# Sheet1.net
KiCad netlist of a schematic drawn in Altium Designer
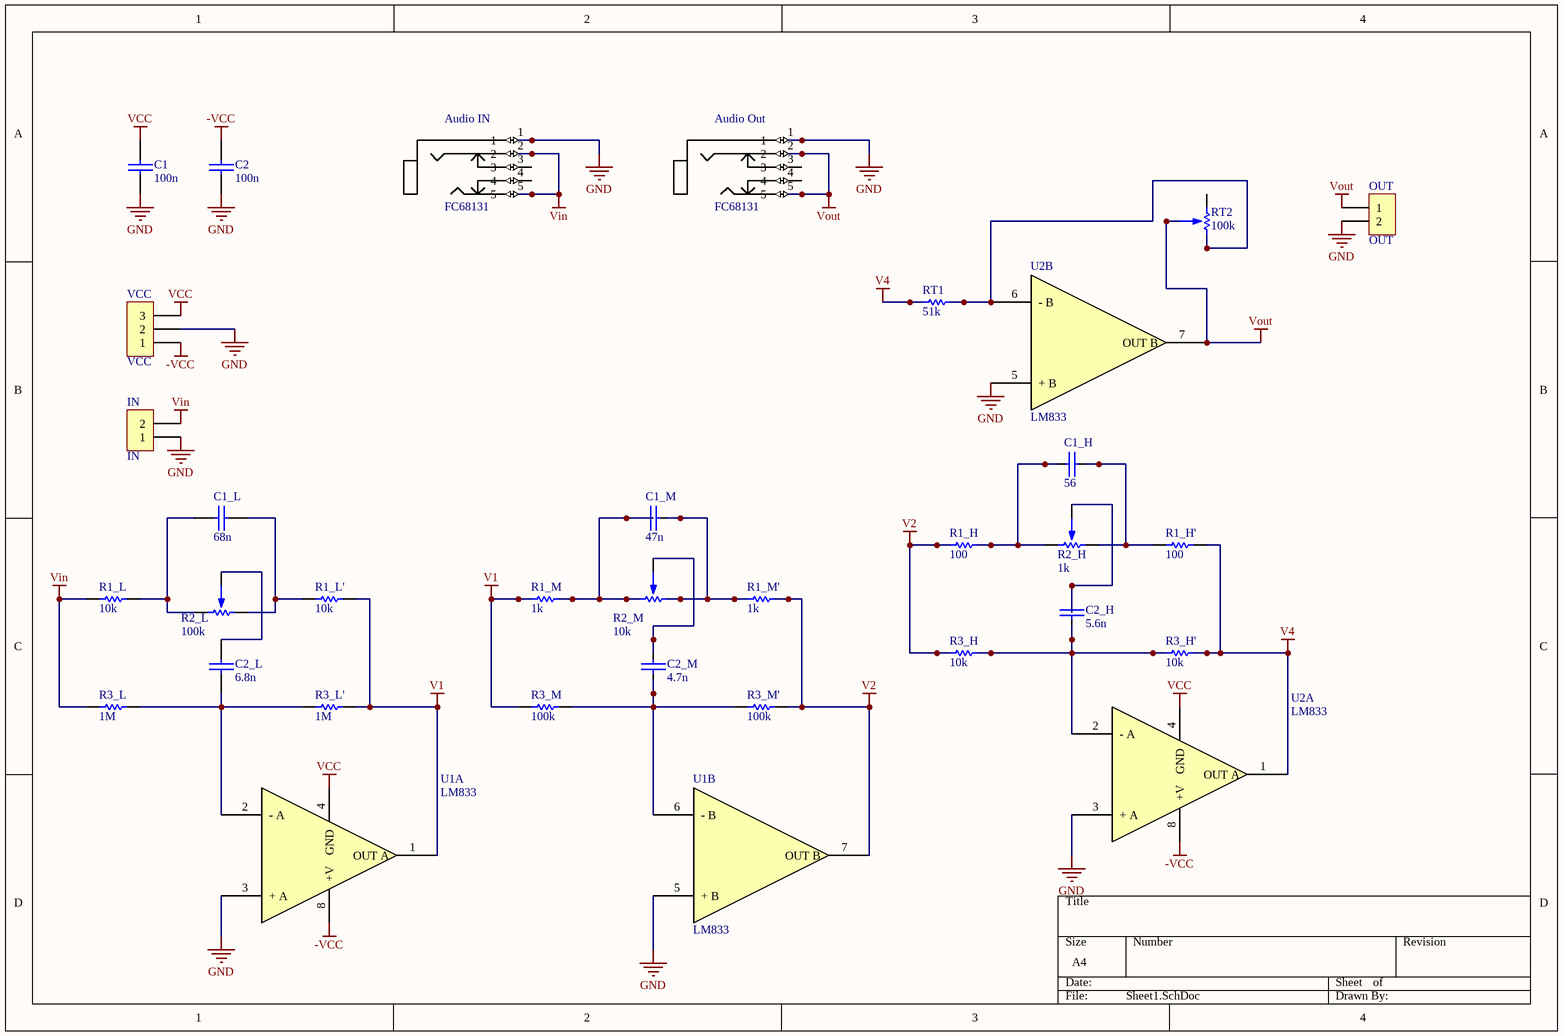
[diagram p0: Sheet1.SchDoc]

(export (version "E")
  (design (tool "Eeschema 10.0.6"))
  (components
    (comp (ref "Audio IN")
      (value "FC68131")
      (footprint "*FC68131-5P")
      (description "Stereo Jack, 3.5mm, 3pos, Pcb")
      (fields (field (name "MF") "Cliff"))
      (libsource (lib "FC68131") (part "FC68131"))
    )
    (comp (ref "Audio Out")
      (value "FC68131")
      (footprint "*FC68131-5P")
      (description "Stereo Jack, 3.5mm, 3pos, Pcb")
      (fields (field (name "MF") "Cliff"))
      (libsource (lib "FC68131") (part "FC68131"))
    )
    (comp (ref "C1") (value "100n") (footprint "0805") (libsource (lib "LIBEBAL") (part "CAP")))
    (comp (ref "C1_H") (value "56") (footprint "0805") (libsource (lib "LIBEBAL") (part "CAP")))
    (comp (ref "C1_L") (value "68n") (footprint "0805") (libsource (lib "LIBEBAL") (part "CAP")))
    (comp (ref "C1_M") (value "47n") (footprint "0805") (libsource (lib "LIBEBAL") (part "CAP")))
    (comp (ref "C2") (value "100n") (footprint "0805") (libsource (lib "LIBEBAL") (part "CAP")))
    (comp (ref "C2_H") (value "5.6n") (footprint "0805") (libsource (lib "LIBEBAL") (part "CAP")))
    (comp (ref "C2_L") (value "6.8n") (footprint "0805") (libsource (lib "LIBEBAL") (part "CAP")))
    (comp (ref "C2_M") (value "4.7n") (footprint "0805") (libsource (lib "LIBEBAL") (part "CAP")))
    (comp (ref "IN") (value "IN") (footprint "BORNERA2") (libsource (lib "LIB PIO IX") (part "BORNERA 2")))
    (comp (ref "OUT") (value "OUT") (footprint "BORNERA2") (libsource (lib "LIBEBAL") (part "BORNERA 2")))
    (comp (ref "R1_H") (value "100") (footprint "0805") (libsource (lib "LIBEBAL") (part "RES")))
    (comp (ref "R1_H'") (value "100") (footprint "0805") (libsource (lib "LIBEBAL") (part "RES")))
    (comp (ref "R1_L") (value "10k") (footprint "0805") (libsource (lib "LIBEBAL") (part "RES")))
    (comp (ref "R1_L'") (value "10k") (footprint "0805") (libsource (lib "LIBEBAL") (part "RES")))
    (comp (ref "R1_M") (value "1k") (footprint "0805") (libsource (lib "LIBEBAL") (part "RES")))
    (comp (ref "R1_M'") (value "1k") (footprint "0805") (libsource (lib "LIBEBAL") (part "RES")))
    (comp (ref "R2_H")
      (value "1k")
      (footprint "POTENCIOMETRO")
      (libsource (lib "LIBEBAL") (part "POTENCIOMETRO"))
    )
    (comp (ref "R2_L")
      (value "100k")
      (footprint "POTENCIOMETRO")
      (libsource (lib "LIBEBAL") (part "POTENCIOMETRO"))
    )
    (comp (ref "R2_M")
      (value "10k")
      (footprint "POTENCIOMETRO")
      (libsource (lib "LIBEBAL") (part "POTENCIOMETRO"))
    )
    (comp (ref "R3_H") (value "10k") (footprint "0805") (libsource (lib "LIBEBAL") (part "RES")))
    (comp (ref "R3_H'") (value "10k") (footprint "0805") (libsource (lib "LIBEBAL") (part "RES")))
    (comp (ref "R3_L") (value "1M") (footprint "1206") (libsource (lib "LIBEBAL") (part "RES")))
    (comp (ref "R3_L'") (value "1M") (footprint "1206") (libsource (lib "LIBEBAL") (part "RES")))
    (comp (ref "R3_M") (value "100k") (footprint "0805") (libsource (lib "LIBEBAL") (part "RES")))
    (comp (ref "R3_M'") (value "100k") (footprint "0805") (libsource (lib "LIBEBAL") (part "RES")))
    (comp (ref "RT1") (value "51k") (footprint "0805") (libsource (lib "LIBEBAL") (part "RES")))
    (comp (ref "RT2")
      (value "100k")
      (footprint "POTENCIOMETRO")
      (libsource (lib "LIBEBAL") (part "POTENCIOMETRO"))
    )
    (comp (ref "U1")
      (value "LM833")
      (footprint "DIP8")
      (description "Dual Audio Operational Amplifier")
      (libsource (lib "LIBEBAL") (part "LM833"))
    )
    (comp (ref "U2")
      (value "LM833")
      (footprint "DIP8")
      (description "Dual Audio Operational Amplifier")
      (libsource (lib "LIBEBAL") (part "LM833"))
    )
    (comp (ref "VCC") (value "VCC") (footprint "BORNERA3") (libsource (lib "LIBEBAL") (part "BORNERA 3")))
  )
  (nets
    (net (code "1") (name "-VCC") (class "Default")
      (node (ref "C2") (pin "1") (pinfunction "1_1") (pintype "passive"))
      (node (ref "U1") (pin "8") (pinfunction "+V_8") (pintype "passive"))
      (node (ref "U2") (pin "8") (pinfunction "+V_8") (pintype "passive"))
      (node (ref "VCC") (pin "1") (pinfunction "1_1") (pintype "passive"))
    )
    (net (code "2") (name "GND") (class "Default")
      (node (ref "Audio IN") (pin "1") (pinfunction "1_1") (pintype "bidirectional"))
      (node (ref "Audio Out") (pin "1") (pinfunction "1_1") (pintype "bidirectional"))
      (node (ref "C1") (pin "2") (pinfunction "2_2") (pintype "passive"))
      (node (ref "C2") (pin "2") (pinfunction "2_2") (pintype "passive"))
      (node (ref "IN") (pin "1") (pinfunction "1_1") (pintype "passive"))
      (node (ref "OUT") (pin "2") (pinfunction "2_2") (pintype "passive"))
      (node (ref "U1") (pin "3") (pinfunction "+_A_3") (pintype "passive"))
      (node (ref "U1") (pin "5") (pinfunction "+_B_5") (pintype "passive"))
      (node (ref "U2") (pin "3") (pinfunction "+_A_3") (pintype "passive"))
      (node (ref "U2") (pin "5") (pinfunction "+_B_5") (pintype "passive"))
      (node (ref "VCC") (pin "2") (pinfunction "2_2") (pintype "passive"))
    )
    (net (code "3") (name "Net-(C1_H-Pad1)") (class "Default")
      (node (ref "C1_H") (pin "1") (pinfunction "1_1") (pintype "passive"))
      (node (ref "R1_H") (pin "2") (pinfunction "2_2") (pintype "passive"))
      (node (ref "R2_H") (pin "1") (pinfunction "1_1") (pintype "passive"))
    )
    (net (code "4") (name "Net-(C1_H-Pad2)") (class "Default")
      (node (ref "C1_H") (pin "2") (pinfunction "2_2") (pintype "passive"))
      (node (ref "R1_H'") (pin "1") (pinfunction "1_1") (pintype "passive"))
      (node (ref "R2_H") (pin "3") (pinfunction "3_3") (pintype "passive"))
    )
    (net (code "5") (name "Net-(C1_L-Pad1)") (class "Default")
      (node (ref "C1_L") (pin "1") (pinfunction "1_1") (pintype "passive"))
      (node (ref "R1_L") (pin "2") (pinfunction "2_2") (pintype "passive"))
      (node (ref "R2_L") (pin "1") (pinfunction "1_1") (pintype "passive"))
    )
    (net (code "6") (name "Net-(C1_L-Pad2)") (class "Default")
      (node (ref "C1_L") (pin "2") (pinfunction "2_2") (pintype "passive"))
      (node (ref "R1_L'") (pin "1") (pinfunction "1_1") (pintype "passive"))
      (node (ref "R2_L") (pin "3") (pinfunction "3_3") (pintype "passive"))
    )
    (net (code "7") (name "Net-(C1_M-Pad1)") (class "Default")
      (node (ref "C1_M") (pin "1") (pinfunction "1_1") (pintype "passive"))
      (node (ref "R1_M") (pin "2") (pinfunction "2_2") (pintype "passive"))
      (node (ref "R2_M") (pin "1") (pinfunction "1_1") (pintype "passive"))
    )
    (net (code "8") (name "Net-(C1_M-Pad2)") (class "Default")
      (node (ref "C1_M") (pin "2") (pinfunction "2_2") (pintype "passive"))
      (node (ref "R1_M'") (pin "1") (pinfunction "1_1") (pintype "passive"))
      (node (ref "R2_M") (pin "3") (pinfunction "3_3") (pintype "passive"))
    )
    (net (code "9") (name "Net-(C2_H-Pad1)") (class "Default")
      (node (ref "C2_H") (pin "1") (pinfunction "1_1") (pintype "passive"))
      (node (ref "R2_H") (pin "2") (pinfunction "2_2") (pintype "passive"))
    )
    (net (code "10") (name "Net-(C2_L-Pad1)") (class "Default")
      (node (ref "C2_L") (pin "1") (pinfunction "1_1") (pintype "passive"))
      (node (ref "R2_L") (pin "2") (pinfunction "2_2") (pintype "passive"))
    )
    (net (code "11") (name "Net-(C2_M-Pad1)") (class "Default")
      (node (ref "C2_M") (pin "1") (pinfunction "1_1") (pintype "passive"))
      (node (ref "R2_M") (pin "2") (pinfunction "2_2") (pintype "passive"))
    )
    (net (code "12") (name "Net-(U1A--_A)") (class "Default")
      (node (ref "C2_L") (pin "2") (pinfunction "2_2") (pintype "passive"))
      (node (ref "R3_L") (pin "2") (pinfunction "2_2") (pintype "passive"))
      (node (ref "R3_L'") (pin "1") (pinfunction "1_1") (pintype "passive"))
      (node (ref "U1") (pin "2") (pinfunction "-_A_2") (pintype "passive"))
    )
    (net (code "13") (name "Net-(U1B--_B)") (class "Default")
      (node (ref "C2_M") (pin "2") (pinfunction "2_2") (pintype "passive"))
      (node (ref "R3_M") (pin "2") (pinfunction "2_2") (pintype "passive"))
      (node (ref "R3_M'") (pin "1") (pinfunction "1_1") (pintype "passive"))
      (node (ref "U1") (pin "6") (pinfunction "-_B_6") (pintype "passive"))
    )
    (net (code "14") (name "Net-(U2A--_A)") (class "Default")
      (node (ref "C2_H") (pin "2") (pinfunction "2_2") (pintype "passive"))
      (node (ref "R3_H") (pin "2") (pinfunction "2_2") (pintype "passive"))
      (node (ref "R3_H'") (pin "1") (pinfunction "1_1") (pintype "passive"))
      (node (ref "U2") (pin "2") (pinfunction "-_A_2") (pintype "passive"))
    )
    (net (code "15") (name "Net-(U2B--_B)") (class "Default")
      (node (ref "RT1") (pin "2") (pinfunction "2_2") (pintype "passive"))
      (node (ref "RT2") (pin "1") (pinfunction "1_1") (pintype "passive"))
      (node (ref "U2") (pin "6") (pinfunction "-_B_6") (pintype "passive"))
    )
    (net (code "16") (name "V1") (class "Default")
      (node (ref "R1_L'") (pin "2") (pinfunction "2_2") (pintype "passive"))
      (node (ref "R1_M") (pin "1") (pinfunction "1_1") (pintype "passive"))
      (node (ref "R3_L'") (pin "2") (pinfunction "2_2") (pintype "passive"))
      (node (ref "R3_M") (pin "1") (pinfunction "1_1") (pintype "passive"))
      (node (ref "U1") (pin "1") (pinfunction "OUT_A_1") (pintype "passive"))
    )
    (net (code "17") (name "V2") (class "Default")
      (node (ref "R1_H") (pin "1") (pinfunction "1_1") (pintype "passive"))
      (node (ref "R1_M'") (pin "2") (pinfunction "2_2") (pintype "passive"))
      (node (ref "R3_H") (pin "1") (pinfunction "1_1") (pintype "passive"))
      (node (ref "R3_M'") (pin "2") (pinfunction "2_2") (pintype "passive"))
      (node (ref "U1") (pin "7") (pinfunction "OUT_B_7") (pintype "passive"))
    )
    (net (code "18") (name "V4") (class "Default")
      (node (ref "R1_H'") (pin "2") (pinfunction "2_2") (pintype "passive"))
      (node (ref "R3_H'") (pin "2") (pinfunction "2_2") (pintype "passive"))
      (node (ref "RT1") (pin "1") (pinfunction "1_1") (pintype "passive"))
      (node (ref "U2") (pin "1") (pinfunction "OUT_A_1") (pintype "passive"))
    )
    (net (code "19") (name "VCC") (class "Default")
      (node (ref "C1") (pin "1") (pinfunction "1_1") (pintype "passive"))
      (node (ref "U1") (pin "4") (pinfunction "GND_4") (pintype "passive"))
      (node (ref "U2") (pin "4") (pinfunction "GND_4") (pintype "passive"))
      (node (ref "VCC") (pin "3") (pinfunction "3_3") (pintype "passive"))
    )
    (net (code "20") (name "Vin") (class "Default")
      (node (ref "Audio IN") (pin "2") (pinfunction "2_2") (pintype "bidirectional"))
      (node (ref "Audio IN") (pin "5") (pinfunction "5_5") (pintype "bidirectional"))
      (node (ref "IN") (pin "2") (pinfunction "2_2") (pintype "passive"))
      (node (ref "R1_L") (pin "1") (pinfunction "1_1") (pintype "passive"))
      (node (ref "R3_L") (pin "1") (pinfunction "1_1") (pintype "passive"))
    )
    (net (code "21") (name "Vout") (class "Default")
      (node (ref "Audio Out") (pin "2") (pinfunction "2_2") (pintype "bidirectional"))
      (node (ref "Audio Out") (pin "5") (pinfunction "5_5") (pintype "bidirectional"))
      (node (ref "OUT") (pin "1") (pinfunction "1_1") (pintype "passive"))
      (node (ref "RT2") (pin "2") (pinfunction "2_2") (pintype "passive"))
      (node (ref "U2") (pin "7") (pinfunction "OUT_B_7") (pintype "passive"))
    )
    (net (code "22") (name "unconnected-(Audio IN-Pad3)") (class "Default")
      (node (ref "Audio IN") (pin "3") (pinfunction "3_3") (pintype "bidirectional"))
    )
    (net (code "23") (name "unconnected-(Audio IN-Pad4)") (class "Default")
      (node (ref "Audio IN") (pin "4") (pinfunction "4_4") (pintype "bidirectional"))
    )
    (net (code "24") (name "unconnected-(Audio Out-Pad3)") (class "Default")
      (node (ref "Audio Out") (pin "3") (pinfunction "3_3") (pintype "bidirectional"))
    )
    (net (code "25") (name "unconnected-(Audio Out-Pad4)") (class "Default")
      (node (ref "Audio Out") (pin "4") (pinfunction "4_4") (pintype "bidirectional"))
    )
    (net (code "26") (name "unconnected-(RT2-Pad3)") (class "Default")
      (node (ref "RT2") (pin "3") (pinfunction "3_3") (pintype "passive"))
    )
  )
)
